# ARE134H.net
KiCad netlist of a schematic drawn in Altium Designer
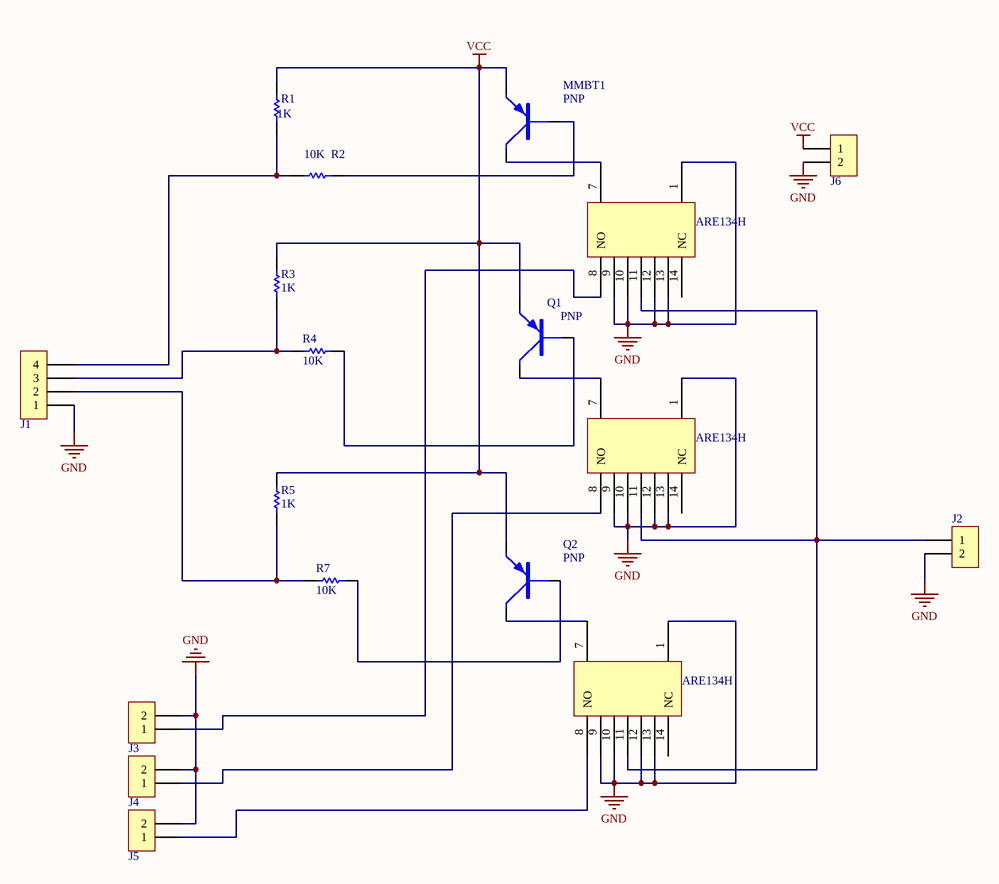
[diagram p0: ARE134H.SchDoc]

(export (version "E")
  (design (tool "Eeschema 10.0.6"))
  (components
    (comp (ref "1") (value "ARE134H") (footprint "DIP14") (libsource (lib "ARE134H") (part "Component_1")))
    (comp (ref "2") (value "ARE134H") (footprint "DIP14") (libsource (lib "ARE134H") (part "Component_1")))
    (comp (ref "3") (value "ARE134H") (footprint "DIP14") (libsource (lib "ARE134H") (part "Component_1")))
    (comp (ref "J1")
      (value "Pin HDR1X4")
      (footprint "Pin HDR1X4/2.54mm-S")
      (libsource (lib "排针") (part "Pin HDR1X4"))
    )
    (comp (ref "J2")
      (value "Pin HDR1X2")
      (footprint "Pin HDR1X2/2.54mm-S")
      (libsource (lib "排针") (part "Pin HDR1X2"))
    )
    (comp (ref "J3")
      (value "Pin HDR1X2")
      (footprint "Pin HDR1X2/2.54mm-S")
      (libsource (lib "") (part "Pin HDR1X2_1"))
    )
    (comp (ref "J4")
      (value "Pin HDR1X2")
      (footprint "Pin HDR1X2/2.54mm-S")
      (libsource (lib "") (part "Pin HDR1X2_1"))
    )
    (comp (ref "J5")
      (value "Pin HDR1X2")
      (footprint "Pin HDR1X2/2.54mm-S")
      (libsource (lib "") (part "Pin HDR1X2_1"))
    )
    (comp (ref "J6")
      (value "Pin HDR1X2")
      (footprint "Pin HDR1X2/2.54mm-S")
      (libsource (lib "排针") (part "Pin HDR1X2"))
    )
    (comp (ref "MMBT1")
      (value "PNP")
      (footprint "SOT-23")
      (description "PNP三极管")
      (libsource (lib "三极管") (part "PNP"))
    )
    (comp (ref "Q1")
      (value "PNP")
      (footprint "SOT-23")
      (description "PNP三极管")
      (libsource (lib "三极管") (part "PNP"))
    )
    (comp (ref "Q2")
      (value "PNP")
      (footprint "SOT-23")
      (description "PNP三极管")
      (libsource (lib "三极管") (part "PNP"))
    )
    (comp (ref "R1")
      (value "1K")
      (footprint "0805R")
      (fields (field (name "Comment") "RES"))
      (libsource (lib "电阻") (part "RES"))
    )
    (comp (ref "R2")
      (value "10K")
      (footprint "0805R")
      (fields (field (name "Comment") "RES"))
      (libsource (lib "电阻") (part "RES"))
    )
    (comp (ref "R3")
      (value "1K")
      (footprint "0805R")
      (fields (field (name "Comment") "RES"))
      (libsource (lib "电阻") (part "RES"))
    )
    (comp (ref "R4")
      (value "10K")
      (footprint "0805R")
      (fields (field (name "Comment") "RES"))
      (libsource (lib "电阻") (part "RES"))
    )
    (comp (ref "R5")
      (value "1K")
      (footprint "0805R")
      (fields (field (name "Comment") "RES"))
      (libsource (lib "电阻") (part "RES"))
    )
    (comp (ref "R7")
      (value "10K")
      (footprint "0805R")
      (fields (field (name "Comment") "RES"))
      (libsource (lib "电阻") (part "RES"))
    )
  )
  (nets
    (net (code "1") (name "GND") (class "Default")
      (node (ref "1") (pin "1") (pintype "open_collector"))
      (node (ref "1") (pin "10") (pintype "open_collector"))
      (node (ref "1") (pin "12") (pinfunction "12_12") (pintype "open_collector"))
      (node (ref "1") (pin "13") (pinfunction "13_13") (pintype "open_collector"))
      (node (ref "1") (pin "9") (pintype "open_collector"))
      (node (ref "2") (pin "1") (pintype "open_collector"))
      (node (ref "2") (pin "10") (pintype "open_collector"))
      (node (ref "2") (pin "12") (pinfunction "12_12") (pintype "open_collector"))
      (node (ref "2") (pin "13") (pinfunction "13_13") (pintype "open_collector"))
      (node (ref "2") (pin "9") (pintype "open_collector"))
      (node (ref "3") (pin "1") (pintype "open_collector"))
      (node (ref "3") (pin "10") (pintype "open_collector"))
      (node (ref "3") (pin "12") (pinfunction "12_12") (pintype "open_collector"))
      (node (ref "3") (pin "13") (pinfunction "13_13") (pintype "open_collector"))
      (node (ref "3") (pin "9") (pintype "open_collector"))
      (node (ref "J1") (pin "1") (pinfunction "1_1") (pintype "passive"))
      (node (ref "J2") (pin "2") (pinfunction "2_2") (pintype "passive"))
      (node (ref "J3") (pin "2") (pinfunction "2_2") (pintype "passive"))
      (node (ref "J4") (pin "2") (pinfunction "2_2") (pintype "passive"))
      (node (ref "J5") (pin "2") (pinfunction "2_2") (pintype "passive"))
      (node (ref "J6") (pin "2") (pinfunction "2_2") (pintype "passive"))
    )
    (net (code "2") (name "Net-(1-NO)") (class "Default")
      (node (ref "1") (pin "8") (pinfunction "NO_8") (pintype "open_collector"))
      (node (ref "J3") (pin "1") (pinfunction "1_1") (pintype "passive"))
    )
    (net (code "3") (name "Net-(1-Pad7)") (class "Default")
      (node (ref "1") (pin "7") (pintype "open_collector"))
      (node (ref "MMBT1") (pin "C") (pinfunction "C_C") (pintype "passive"))
    )
    (net (code "4") (name "Net-(1-Pad11)") (class "Default")
      (node (ref "1") (pin "11") (pintype "open_collector"))
      (node (ref "2") (pin "11") (pintype "open_collector"))
      (node (ref "3") (pin "11") (pintype "open_collector"))
      (node (ref "J2") (pin "1") (pinfunction "1_1") (pintype "passive"))
    )
    (net (code "5") (name "Net-(2-NO)") (class "Default")
      (node (ref "2") (pin "8") (pinfunction "NO_8") (pintype "open_collector"))
      (node (ref "J4") (pin "1") (pinfunction "1_1") (pintype "passive"))
    )
    (net (code "6") (name "Net-(2-Pad7)") (class "Default")
      (node (ref "2") (pin "7") (pintype "open_collector"))
      (node (ref "Q1") (pin "C") (pinfunction "C_C") (pintype "passive"))
    )
    (net (code "7") (name "Net-(3-NO)") (class "Default")
      (node (ref "3") (pin "8") (pinfunction "NO_8") (pintype "open_collector"))
      (node (ref "J5") (pin "1") (pinfunction "1_1") (pintype "passive"))
    )
    (net (code "8") (name "Net-(3-Pad7)") (class "Default")
      (node (ref "3") (pin "7") (pintype "open_collector"))
      (node (ref "Q2") (pin "C") (pinfunction "C_C") (pintype "passive"))
    )
    (net (code "9") (name "Net-(J1-Pad2)") (class "Default")
      (node (ref "J1") (pin "2") (pinfunction "2_2") (pintype "passive"))
      (node (ref "R5") (pin "1") (pinfunction "1_1") (pintype "passive"))
      (node (ref "R7") (pin "1") (pinfunction "1_1") (pintype "passive"))
    )
    (net (code "10") (name "Net-(J1-Pad3)") (class "Default")
      (node (ref "J1") (pin "3") (pinfunction "3_3") (pintype "passive"))
      (node (ref "R3") (pin "1") (pinfunction "1_1") (pintype "passive"))
      (node (ref "R4") (pin "1") (pinfunction "1_1") (pintype "passive"))
    )
    (net (code "11") (name "Net-(J1-Pad4)") (class "Default")
      (node (ref "J1") (pin "4") (pinfunction "4_4") (pintype "passive"))
      (node (ref "R1") (pin "1") (pinfunction "1_1") (pintype "passive"))
      (node (ref "R2") (pin "1") (pinfunction "1_1") (pintype "passive"))
    )
    (net (code "12") (name "Net-(MMBT1-PadB)") (class "Default")
      (node (ref "MMBT1") (pin "B") (pinfunction "B_B") (pintype "passive"))
      (node (ref "R2") (pin "2") (pinfunction "2_2") (pintype "passive"))
    )
    (net (code "13") (name "Net-(Q1-PadB)") (class "Default")
      (node (ref "Q1") (pin "B") (pinfunction "B_B") (pintype "passive"))
      (node (ref "R4") (pin "2") (pinfunction "2_2") (pintype "passive"))
    )
    (net (code "14") (name "Net-(Q2-PadB)") (class "Default")
      (node (ref "Q2") (pin "B") (pinfunction "B_B") (pintype "passive"))
      (node (ref "R7") (pin "2") (pinfunction "2_2") (pintype "passive"))
    )
    (net (code "15") (name "VCC") (class "Default")
      (node (ref "J6") (pin "1") (pinfunction "1_1") (pintype "passive"))
      (node (ref "MMBT1") (pin "E") (pinfunction "E_E") (pintype "passive"))
      (node (ref "Q1") (pin "E") (pinfunction "E_E") (pintype "passive"))
      (node (ref "Q2") (pin "E") (pinfunction "E_E") (pintype "passive"))
      (node (ref "R1") (pin "2") (pinfunction "2_2") (pintype "passive"))
      (node (ref "R3") (pin "2") (pinfunction "2_2") (pintype "passive"))
      (node (ref "R5") (pin "2") (pinfunction "2_2") (pintype "passive"))
    )
    (net (code "16") (name "unconnected-(1-NC-Pad14)") (class "Default")
      (node (ref "1") (pin "14") (pinfunction "NC_14") (pintype "open_collector"))
    )
    (net (code "17") (name "unconnected-(2-NC-Pad14)") (class "Default")
      (node (ref "2") (pin "14") (pinfunction "NC_14") (pintype "open_collector"))
    )
    (net (code "18") (name "unconnected-(3-NC-Pad14)") (class "Default")
      (node (ref "3") (pin "14") (pinfunction "NC_14") (pintype "open_collector"))
    )
  )
)
